# Stash_cap_board_hardctrl_rev_H.net
KiCad netlist of a schematic drawn in EAGLE
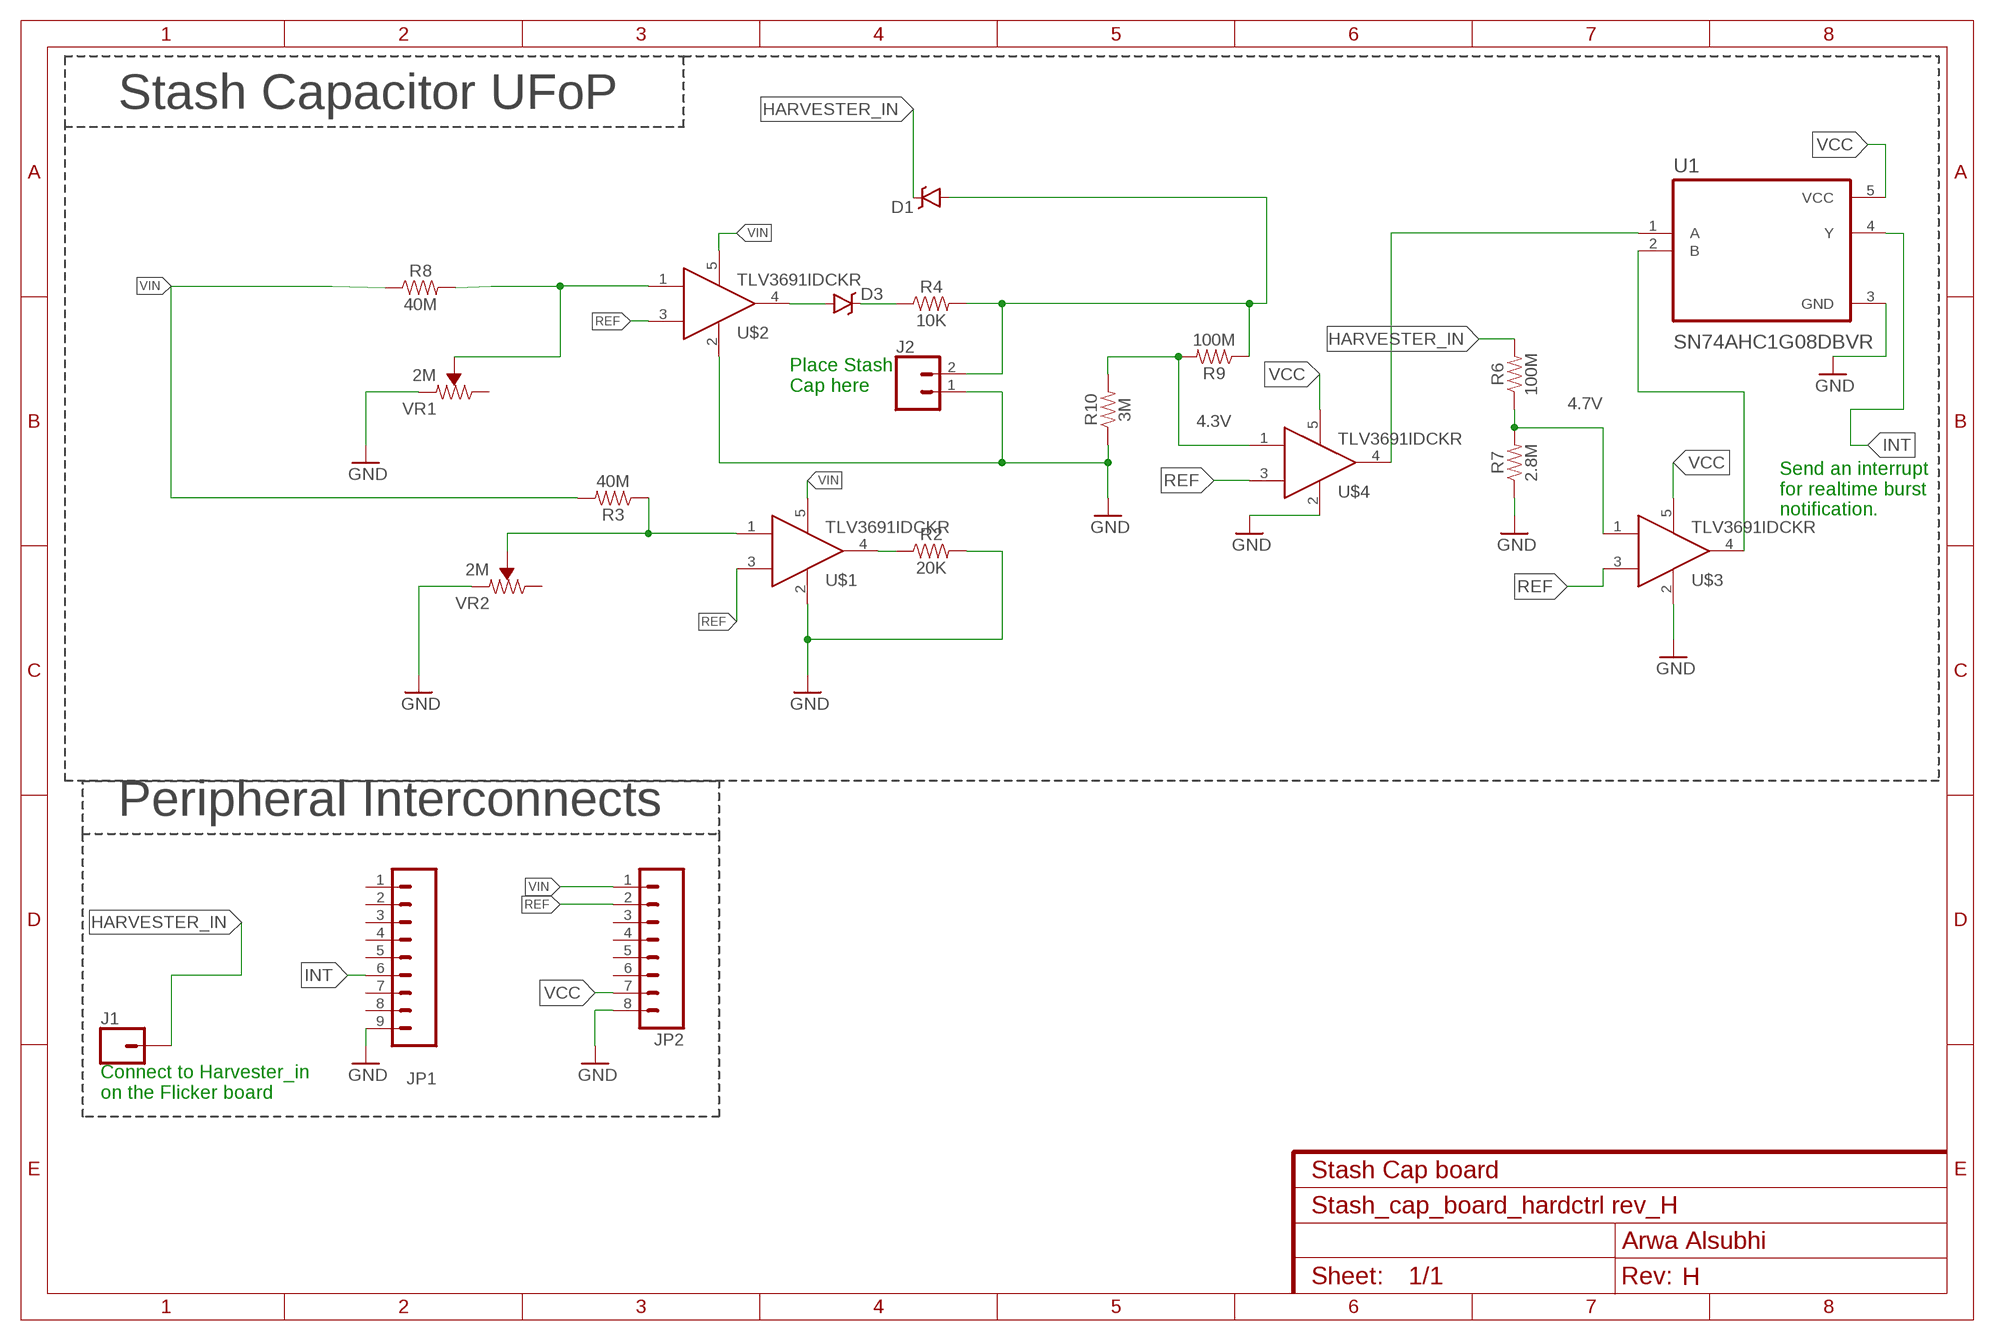
[diagram p0: schematic, sheet 1]

(export (version "E")
  (design (tool "Eeschema 10.0.6"))
  (components
    (comp (ref "D1")
      (value "RB751")
      (footprint "eagle-import:SOD-523")
      (fields (field (name "MPN") "BAS40-02V-V-G-08"))
      (libsource (lib "eagle-import") (part "DIODE-SCHOTTKY-RB751"))
    )
    (comp (ref "D3")
      (value "RB751")
      (footprint "eagle-import:SOD-523")
      (fields (field (name "MPN") "BAS40-02V-V-G-08"))
      (libsource (lib "eagle-import") (part "DIODE-SCHOTTKY-RB751"))
    )
    (comp (ref "J1")
      (value "CONN_01")
      (footprint "eagle-import:1X01")
      (libsource (lib "eagle-import") (part "CONN_01"))
    )
    (comp (ref "J2")
      (value "CONN_02")
      (footprint "eagle-import:1X02")
      (libsource (lib "eagle-import") (part "CONN_02"))
    )
    (comp (ref "JP1")
      (value "M091.27MM")
      (footprint "eagle-import:1X09-1.27MM")
      (fields (field (name "MANUFACTURERPARTNUMBER") "GRPB091VWVN-RC ") (field (name "MPN") "GRPB091VWVN-RC"))
      (libsource (lib "eagle-import") (part "M091.27MM"))
    )
    (comp (ref "JP2")
      (value "M081.27MM")
      (footprint "eagle-import:1X08-1.27MM")
      (fields (field (name "MANUFACTURERPARTNUMBER") "GRPB081VWVN-RC "))
      (libsource (lib "eagle-import") (part "M081.27MM"))
    )
    (comp (ref "R2")
      (value "20K")
      (footprint "eagle-import:0805")
      (libsource (lib "eagle-import") (part "0.3OHM-0805-1/8W-1%"))
    )
    (comp (ref "R3")
      (value "40M")
      (footprint "eagle-import:0805")
      (libsource (lib "eagle-import") (part "0.3OHM-0805-1/8W-1%"))
    )
    (comp (ref "R4")
      (value "10K")
      (footprint "eagle-import:0603")
      (libsource (lib "eagle-import") (part "0603-RESISTOR-0603-1/10W-1%"))
    )
    (comp (ref "R6")
      (value "100M")
      (footprint "eagle-import:0805")
      (libsource (lib "eagle-import") (part "0.3OHM-0805-1/8W-1%"))
    )
    (comp (ref "R7")
      (value "2.8M")
      (footprint "eagle-import:0805")
      (libsource (lib "eagle-import") (part "0.3OHM-0805-1/8W-1%"))
    )
    (comp (ref "R8")
      (value "40M")
      (footprint "eagle-import:0805")
      (libsource (lib "eagle-import") (part "0.3OHM-0805-1/8W-1%"))
    )
    (comp (ref "R9")
      (value "100M")
      (footprint "eagle-import:0805")
      (libsource (lib "eagle-import") (part "0.3OHM-0805-1/8W-1%"))
    )
    (comp (ref "R10")
      (value "3M")
      (footprint "eagle-import:0805")
      (libsource (lib "eagle-import") (part "0.3OHM-0805-1/8W-1%"))
    )
    (comp (ref "U$1")
      (value "TLV3691IDCKR")
      (footprint "eagle-import:SOT353")
      (libsource (lib "eagle-import") (part "TLV3691IDCKR"))
    )
    (comp (ref "U$2")
      (value "TLV3691IDCKR")
      (footprint "eagle-import:SOT353")
      (libsource (lib "eagle-import") (part "TLV3691IDCKR"))
    )
    (comp (ref "U$3")
      (value "TLV3691IDCKR")
      (footprint "eagle-import:SOT353")
      (libsource (lib "eagle-import") (part "TLV3691IDCKR"))
    )
    (comp (ref "U$4")
      (value "TLV3691IDCKR")
      (footprint "eagle-import:SOT353")
      (libsource (lib "eagle-import") (part "TLV3691IDCKR"))
    )
    (comp (ref "U1")
      (value "SN74AHC1G08DBVR")
      (footprint "eagle-import:SOT95P280X145-5N")
      (fields (field (name "MF") "Texas Instruments"))
      (libsource (lib "eagle-import") (part "SN74AHC1G08DBVR"))
    )
    (comp (ref "VR1")
      (value "2M")
      (footprint "eagle-import:TRIMPOT-SMD-3MM-CLOSED")
      (libsource (lib "eagle-import") (part "TRIMPOT-SMD-3MM-CLOSED-1/8W-20%"))
    )
    (comp (ref "VR2")
      (value "2M")
      (footprint "eagle-import:TRIMPOT-SMD-3MM-CLOSED")
      (libsource (lib "eagle-import") (part "TRIMPOT-SMD-3MM-CLOSED-1/8W-20%"))
    )
  )
  (nets
    (net (code "1") (name "GND") (class "Default")
      (node (ref "J2") (pin "1") (pinfunction "1_1") (pintype "passive"))
      (node (ref "JP1") (pin "9") (pinfunction "9_9") (pintype "passive"))
      (node (ref "JP2") (pin "8") (pinfunction "8_8") (pintype "passive"))
      (node (ref "R10") (pin "1") (pinfunction "1_1") (pintype "passive"))
      (node (ref "R2") (pin "2") (pinfunction "2_2") (pintype "passive"))
      (node (ref "R7") (pin "1") (pinfunction "1_1") (pintype "passive"))
      (node (ref "U$1") (pin "2") (pinfunction "2_2") (pintype "bidirectional"))
      (node (ref "U$2") (pin "2") (pinfunction "2_2") (pintype "bidirectional"))
      (node (ref "U$3") (pin "2") (pinfunction "2_2") (pintype "bidirectional"))
      (node (ref "U$4") (pin "2") (pinfunction "2_2") (pintype "bidirectional"))
      (node (ref "U1") (pin "3") (pinfunction "GND_3") (pintype "power_in"))
      (node (ref "VR1") (pin "1") (pinfunction "CCW_1") (pintype "passive"))
      (node (ref "VR2") (pin "1") (pinfunction "CCW_1") (pintype "passive"))
    )
    (net (code "2") (name "HARVESTER_IN") (class "Default")
      (node (ref "D1") (pin "C") (pinfunction "C_C") (pintype "passive"))
      (node (ref "J1") (pin "1") (pinfunction "1_1") (pintype "passive"))
      (node (ref "R6") (pin "2") (pinfunction "2_2") (pintype "passive"))
    )
    (net (code "3") (name "INT") (class "Default")
      (node (ref "JP1") (pin "6") (pinfunction "6_6") (pintype "passive"))
      (node (ref "U1") (pin "4") (pinfunction "Y_4") (pintype "output"))
    )
    (net (code "4") (name "Net-(D1-PadA)") (class "Default")
      (node (ref "D1") (pin "A") (pinfunction "A_A") (pintype "passive"))
      (node (ref "J2") (pin "2") (pinfunction "2_2") (pintype "passive"))
      (node (ref "R4") (pin "2") (pinfunction "2_2") (pintype "passive"))
      (node (ref "R9") (pin "1") (pinfunction "1_1") (pintype "passive"))
    )
    (net (code "5") (name "Net-(D3-PadA)") (class "Default")
      (node (ref "D3") (pin "A") (pinfunction "A_A") (pintype "passive"))
      (node (ref "U$2") (pin "4") (pinfunction "4_4") (pintype "bidirectional"))
    )
    (net (code "6") (name "Net-(D3-PadC)") (class "Default")
      (node (ref "D3") (pin "C") (pinfunction "C_C") (pintype "passive"))
      (node (ref "R4") (pin "1") (pinfunction "1_1") (pintype "passive"))
    )
    (net (code "7") (name "Net-(R2-Pad1)") (class "Default")
      (node (ref "R2") (pin "1") (pinfunction "1_1") (pintype "passive"))
      (node (ref "U$1") (pin "4") (pinfunction "4_4") (pintype "bidirectional"))
    )
    (net (code "8") (name "Net-(R6-Pad1)") (class "Default")
      (node (ref "R6") (pin "1") (pinfunction "1_1") (pintype "passive"))
      (node (ref "R7") (pin "2") (pinfunction "2_2") (pintype "passive"))
      (node (ref "U$3") (pin "1") (pinfunction "1_1") (pintype "bidirectional"))
    )
    (net (code "9") (name "Net-(R10-Pad2)") (class "Default")
      (node (ref "R10") (pin "2") (pinfunction "2_2") (pintype "passive"))
      (node (ref "R9") (pin "2") (pinfunction "2_2") (pintype "passive"))
      (node (ref "U$4") (pin "1") (pinfunction "1_1") (pintype "bidirectional"))
    )
    (net (code "10") (name "Net-(U1-A)") (class "Default")
      (node (ref "U$4") (pin "4") (pinfunction "4_4") (pintype "bidirectional"))
      (node (ref "U1") (pin "1") (pinfunction "A_1") (pintype "input"))
    )
    (net (code "11") (name "Net-(U1-B)") (class "Default")
      (node (ref "U$3") (pin "4") (pinfunction "4_4") (pintype "bidirectional"))
      (node (ref "U1") (pin "2") (pinfunction "B_2") (pintype "input"))
    )
    (net (code "12") (name "Net-(VR1-WIPER)") (class "Default")
      (node (ref "R8") (pin "2") (pinfunction "2_2") (pintype "passive"))
      (node (ref "U$2") (pin "1") (pinfunction "1_1") (pintype "bidirectional"))
      (node (ref "VR1") (pin "2") (pinfunction "WIPER_2") (pintype "passive"))
    )
    (net (code "13") (name "Net-(VR2-WIPER)") (class "Default")
      (node (ref "R3") (pin "1") (pinfunction "1_1") (pintype "passive"))
      (node (ref "U$1") (pin "1") (pinfunction "1_1") (pintype "bidirectional"))
      (node (ref "VR2") (pin "2") (pinfunction "WIPER_2") (pintype "passive"))
    )
    (net (code "14") (name "REF") (class "Default")
      (node (ref "JP2") (pin "2") (pinfunction "2_2") (pintype "passive"))
      (node (ref "U$1") (pin "3") (pinfunction "3_3") (pintype "bidirectional"))
      (node (ref "U$2") (pin "3") (pinfunction "3_3") (pintype "bidirectional"))
      (node (ref "U$3") (pin "3") (pinfunction "3_3") (pintype "bidirectional"))
      (node (ref "U$4") (pin "3") (pinfunction "3_3") (pintype "bidirectional"))
    )
    (net (code "15") (name "VCC") (class "Default")
      (node (ref "JP2") (pin "7") (pinfunction "7_7") (pintype "passive"))
      (node (ref "U$3") (pin "5") (pinfunction "5_5") (pintype "bidirectional"))
      (node (ref "U$4") (pin "5") (pinfunction "5_5") (pintype "bidirectional"))
      (node (ref "U1") (pin "5") (pinfunction "VCC_5") (pintype "power_in"))
    )
    (net (code "16") (name "VIN") (class "Default")
      (node (ref "JP2") (pin "1") (pinfunction "1_1") (pintype "passive"))
      (node (ref "R3") (pin "2") (pinfunction "2_2") (pintype "passive"))
      (node (ref "R8") (pin "1") (pinfunction "1_1") (pintype "passive"))
      (node (ref "U$1") (pin "5") (pinfunction "5_5") (pintype "bidirectional"))
      (node (ref "U$2") (pin "5") (pinfunction "5_5") (pintype "bidirectional"))
    )
    (net (code "17") (name "unconnected-(JP1-Pad1)") (class "Default")
      (node (ref "JP1") (pin "1") (pinfunction "1_1") (pintype "passive"))
    )
    (net (code "18") (name "unconnected-(JP1-Pad2)") (class "Default")
      (node (ref "JP1") (pin "2") (pinfunction "2_2") (pintype "passive"))
    )
    (net (code "19") (name "unconnected-(JP1-Pad3)") (class "Default")
      (node (ref "JP1") (pin "3") (pinfunction "3_3") (pintype "passive"))
    )
    (net (code "20") (name "unconnected-(JP1-Pad4)") (class "Default")
      (node (ref "JP1") (pin "4") (pinfunction "4_4") (pintype "passive"))
    )
    (net (code "21") (name "unconnected-(JP1-Pad5)") (class "Default")
      (node (ref "JP1") (pin "5") (pinfunction "5_5") (pintype "passive"))
    )
    (net (code "22") (name "unconnected-(JP1-Pad7)") (class "Default")
      (node (ref "JP1") (pin "7") (pinfunction "7_7") (pintype "passive"))
    )
    (net (code "23") (name "unconnected-(JP1-Pad8)") (class "Default")
      (node (ref "JP1") (pin "8") (pinfunction "8_8") (pintype "passive"))
    )
    (net (code "24") (name "unconnected-(JP2-Pad3)") (class "Default")
      (node (ref "JP2") (pin "3") (pinfunction "3_3") (pintype "passive"))
    )
    (net (code "25") (name "unconnected-(JP2-Pad4)") (class "Default")
      (node (ref "JP2") (pin "4") (pinfunction "4_4") (pintype "passive"))
    )
    (net (code "26") (name "unconnected-(JP2-Pad5)") (class "Default")
      (node (ref "JP2") (pin "5") (pinfunction "5_5") (pintype "passive"))
    )
    (net (code "27") (name "unconnected-(JP2-Pad6)") (class "Default")
      (node (ref "JP2") (pin "6") (pinfunction "6_6") (pintype "passive"))
    )
    (net (code "28") (name "unconnected-(VR1-CW-Pad3)") (class "Default")
      (node (ref "VR1") (pin "3") (pinfunction "CW_3") (pintype "passive"))
    )
    (net (code "29") (name "unconnected-(VR2-CW-Pad3)") (class "Default")
      (node (ref "VR2") (pin "3") (pinfunction "CW_3") (pintype "passive"))
    )
  )
)
